# LogicPower.net
KiCad netlist of a schematic drawn in Altium Designer
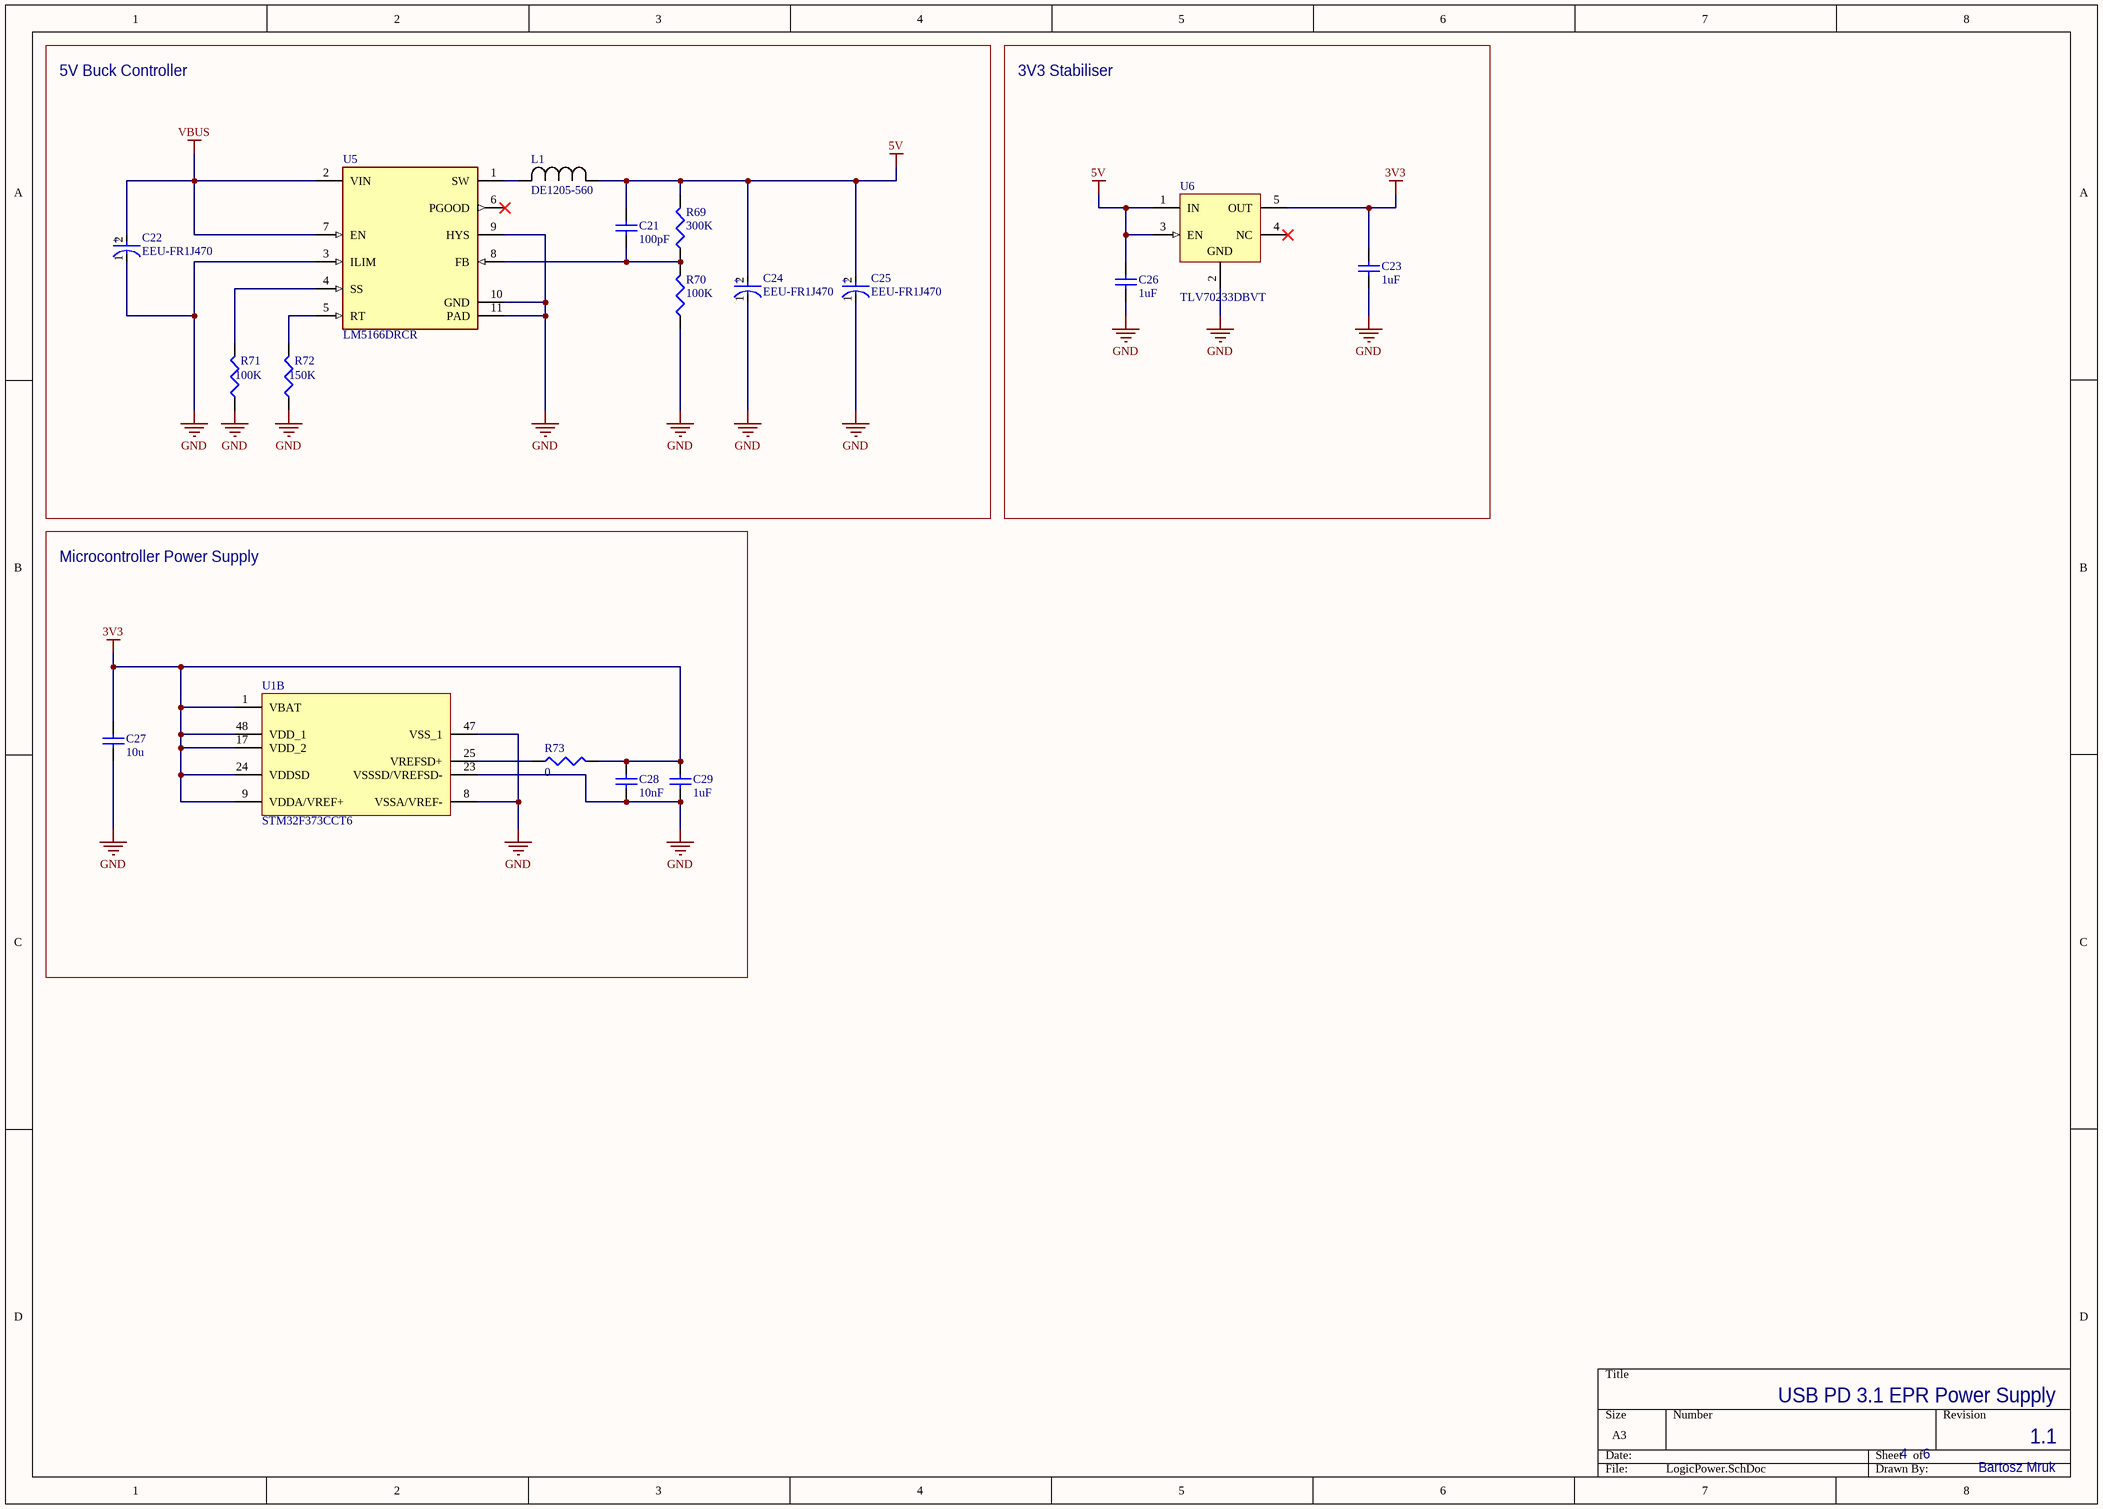
[diagram p0: LogicPower.SchDoc]

(export (version "E")
  (design (tool "Eeschema 10.0.6"))
  (components
    (comp (ref "C21")
      (value "100pF")
      (footprint "C1206")
      (description "Capacitor (Semiconductor SIM Model)")
      (fields (field (name "Comment") "Cap Semi") (field (name "PUBLISHER") "Altium Limited"))
      (libsource (lib "Miscellaneous Devices") (part "Cap Semi"))
    )
    (comp (ref "C22")
      (value "EEU-FR1J470")
      (footprint "FP-EEU-FR1J470-MFG")
      (description "CAP ALUM 47UF 20% 63V RADIAL")
      (fields (field (name "TOLERANCE") "20%") (field (name "VOLTAGE") "63V"))
      (libsource (lib "Altium Content Vault") (part "203bc49f2ac43e59fd269a8c329ed05"))
    )
    (comp (ref "C23")
      (value "1uF")
      (footprint "C1206")
      (description "Capacitor (Semiconductor SIM Model)")
      (fields (field (name "Comment") "Cap Semi") (field (name "PUBLISHER") "Altium Limited"))
      (libsource (lib "Miscellaneous Devices") (part "Cap Semi"))
    )
    (comp (ref "C24")
      (value "EEU-FR1J470")
      (footprint "FP-EEU-FR1J470-MFG")
      (description "CAP ALUM 47UF 20% 63V RADIAL")
      (fields (field (name "TOLERANCE") "20%") (field (name "VOLTAGE") "63V"))
      (libsource (lib "Altium Content Vault") (part "203bc49f2ac43e59fd269a8c329ed05"))
    )
    (comp (ref "C25")
      (value "EEU-FR1J470")
      (footprint "FP-EEU-FR1J470-MFG")
      (description "CAP ALUM 47UF 20% 63V RADIAL")
      (fields (field (name "TOLERANCE") "20%") (field (name "VOLTAGE") "63V"))
      (libsource (lib "Altium Content Vault") (part "203bc49f2ac43e59fd269a8c329ed05"))
    )
    (comp (ref "C26")
      (value "1uF")
      (footprint "C1206")
      (description "Capacitor (Semiconductor SIM Model)")
      (fields (field (name "Comment") "Cap Semi") (field (name "PUBLISHER") "Altium Limited"))
      (libsource (lib "Miscellaneous Devices") (part "Cap Semi"))
    )
    (comp (ref "C27")
      (value "10u")
      (footprint "C1206")
      (description "Capacitor (Semiconductor SIM Model)")
      (fields (field (name "Comment") "Cap Semi") (field (name "PUBLISHER") "Altium Limited"))
      (libsource (lib "Miscellaneous Devices") (part "Cap Semi"))
    )
    (comp (ref "C28")
      (value "10nF")
      (footprint "C1206")
      (description "Capacitor (Semiconductor SIM Model)")
      (fields (field (name "Comment") "Cap Semi") (field (name "PUBLISHER") "Altium Limited"))
      (libsource (lib "Miscellaneous Devices") (part "Cap Semi"))
    )
    (comp (ref "C29")
      (value "1uF")
      (footprint "C1206")
      (description "Capacitor (Semiconductor SIM Model)")
      (fields (field (name "Comment") "Cap Semi") (field (name "PUBLISHER") "Altium Limited"))
      (libsource (lib "Miscellaneous Devices") (part "Cap Semi"))
    )
    (comp (ref "L1")
      (value "DE1205-560")
      (footprint "IND_DE1205_FRC")
      (description "Description")
      (fields (field (name "COPYRIGHT") "Copyright (C) 2025 Ultra Librarian. All rights reserved."))
      (libsource (lib "DE1205-560") (part "DE1205-560"))
    )
    (comp (ref "R69")
      (value "300K")
      (footprint "J1-0603")
      (description "Resistor")
      (fields (field (name "Comment") "Res3") (field (name "PUBLISHER") "Altium Limited"))
      (libsource (lib "Miscellaneous Devices") (part "Res3"))
    )
    (comp (ref "R70")
      (value "100K")
      (footprint "J1-0603")
      (description "Resistor")
      (fields (field (name "Comment") "Res3") (field (name "PUBLISHER") "Altium Limited"))
      (libsource (lib "Miscellaneous Devices") (part "Res3"))
    )
    (comp (ref "R71")
      (value "100K")
      (footprint "J1-0603")
      (description "Resistor")
      (fields (field (name "Comment") "Res3") (field (name "PUBLISHER") "Altium Limited"))
      (libsource (lib "Miscellaneous Devices") (part "Res3"))
    )
    (comp (ref "R72")
      (value "150K")
      (footprint "J1-0603")
      (description "Resistor")
      (fields (field (name "Comment") "Res3") (field (name "PUBLISHER") "Altium Limited"))
      (libsource (lib "Miscellaneous Devices") (part "Res3"))
    )
    (comp (ref "R73")
      (value "0")
      (footprint "J1-0603")
      (description "Resistor")
      (fields (field (name "Comment") "Res3") (field (name "PUBLISHER") "Altium Limited"))
      (libsource (lib "Miscellaneous Devices") (part "Res3"))
    )
    (comp (ref "U1")
      (value "STM32F373CCT6")
      (footprint "STM-LQFP48_M")
      (libsource (lib "Altium Content Vault") (part "MC-ARM-STM32F373-SQ48"))
    )
    (comp (ref "U5")
      (value "LM5166DRCR")
      (footprint "FP-DRC0010J-MFG")
      (description "IC REG BUCK ADJ 500MA 10VSON")
      (fields
        (field (name "OCTOPART") "https://octopart.com/lm5166drcr-texas+instruments-77040222")
        (field (name "MANUFACTURER") "Texas Instruments")
      )
      (libsource (lib "Altium Content Vault") (part "54f7a5ab2ddfda0310545cf18dfc889"))
    )
    (comp (ref "U6")
      (value "TLV70233DBVT")
      (footprint "DBV0005A_M")
      (description "None")
      (libsource (lib "Altium Content Vault") (part "TI-TXX7XXXX-5"))
    )
  )
  (nets
    (net (code "1") (name "3V3") (class "Default")
      (node (ref "C23") (pin "2") (pinfunction "2_2") (pintype "passive"))
      (node (ref "C27") (pin "2") (pinfunction "2_2") (pintype "passive"))
      (node (ref "C28") (pin "2") (pinfunction "2_2") (pintype "passive"))
      (node (ref "C29") (pin "2") (pinfunction "2_2") (pintype "passive"))
      (node (ref "R73") (pin "2") (pinfunction "2_2") (pintype "passive"))
      (node (ref "U1") (pin "1") (pinfunction "VBAT_1") (pintype "power_in"))
      (node (ref "U1") (pin "17") (pinfunction "VDD_2_17") (pintype "power_in"))
      (node (ref "U1") (pin "24") (pinfunction "VDDSD_24") (pintype "power_in"))
      (node (ref "U1") (pin "48") (pinfunction "VDD_1_48") (pintype "power_in"))
      (node (ref "U1") (pin "9") (pinfunction "VDDA/VREF+_9") (pintype "power_in"))
      (node (ref "U6") (pin "5") (pinfunction "OUT_5") (pintype "power_in"))
    )
    (net (code "2") (name "5V") (class "Default")
      (node (ref "C21") (pin "2") (pinfunction "2_2") (pintype "passive"))
      (node (ref "C24") (pin "2") (pinfunction "A_2") (pintype "passive"))
      (node (ref "C25") (pin "2") (pinfunction "A_2") (pintype "passive"))
      (node (ref "C26") (pin "2") (pinfunction "2_2") (pintype "passive"))
      (node (ref "L1") (pin "1") (pinfunction "1_1") (pintype "passive"))
      (node (ref "R69") (pin "2") (pinfunction "2_2") (pintype "passive"))
      (node (ref "U6") (pin "1") (pinfunction "IN_1") (pintype "power_in"))
      (node (ref "U6") (pin "3") (pinfunction "EN_3") (pintype "input"))
    )
    (net (code "3") (name "GND") (class "Default")
      (node (ref "C22") (pin "1") (pinfunction "C_1") (pintype "passive"))
      (node (ref "C23") (pin "1") (pinfunction "1_1") (pintype "passive"))
      (node (ref "C24") (pin "1") (pinfunction "C_1") (pintype "passive"))
      (node (ref "C25") (pin "1") (pinfunction "C_1") (pintype "passive"))
      (node (ref "C26") (pin "1") (pinfunction "1_1") (pintype "passive"))
      (node (ref "C27") (pin "1") (pinfunction "1_1") (pintype "passive"))
      (node (ref "C28") (pin "1") (pinfunction "1_1") (pintype "passive"))
      (node (ref "C29") (pin "1") (pinfunction "1_1") (pintype "passive"))
      (node (ref "R70") (pin "1") (pinfunction "1_1") (pintype "passive"))
      (node (ref "R71") (pin "1") (pinfunction "1_1") (pintype "passive"))
      (node (ref "R72") (pin "1") (pinfunction "1_1") (pintype "passive"))
      (node (ref "U1") (pin "23") (pinfunction "VSSSD/VREFSD-_23") (pintype "power_in"))
      (node (ref "U1") (pin "47") (pinfunction "VSS_1_47") (pintype "power_in"))
      (node (ref "U1") (pin "8") (pinfunction "VSSA/VREF-_8") (pintype "power_in"))
      (node (ref "U5") (pin "10") (pinfunction "GND_10") (pintype "power_in"))
      (node (ref "U5") (pin "11") (pinfunction "PAD_11") (pintype "power_in"))
      (node (ref "U5") (pin "3") (pinfunction "ILIM_3") (pintype "input"))
      (node (ref "U5") (pin "9") (pinfunction "HYS_9") (pintype "passive"))
      (node (ref "U6") (pin "2") (pinfunction "GND_2") (pintype "power_in"))
    )
    (net (code "4") (name "Net-(U1B-VREFSD+)") (class "Default")
      (node (ref "R73") (pin "1") (pinfunction "1_1") (pintype "passive"))
      (node (ref "U1") (pin "25") (pinfunction "VREFSD+_25") (pintype "power_in"))
    )
    (net (code "5") (name "Net-(U5-FB)") (class "Default")
      (node (ref "C21") (pin "1") (pinfunction "1_1") (pintype "passive"))
      (node (ref "R69") (pin "1") (pinfunction "1_1") (pintype "passive"))
      (node (ref "R70") (pin "2") (pinfunction "2_2") (pintype "passive"))
      (node (ref "U5") (pin "8") (pinfunction "FB_8") (pintype "input"))
    )
    (net (code "6") (name "Net-(U5-RT)") (class "Default")
      (node (ref "R72") (pin "2") (pinfunction "2_2") (pintype "passive"))
      (node (ref "U5") (pin "5") (pinfunction "RT_5") (pintype "input"))
    )
    (net (code "7") (name "Net-(U5-SS)") (class "Default")
      (node (ref "R71") (pin "2") (pinfunction "2_2") (pintype "passive"))
      (node (ref "U5") (pin "4") (pinfunction "SS_4") (pintype "input"))
    )
    (net (code "8") (name "Net-(U5-SW)") (class "Default")
      (node (ref "L1") (pin "2") (pinfunction "2_2") (pintype "passive"))
      (node (ref "U5") (pin "1") (pinfunction "SW_1") (pintype "power_in"))
    )
    (net (code "9") (name "VBUS") (class "Default")
      (node (ref "C22") (pin "2") (pinfunction "A_2") (pintype "passive"))
      (node (ref "U5") (pin "2") (pinfunction "VIN_2") (pintype "power_in"))
      (node (ref "U5") (pin "7") (pinfunction "EN_7") (pintype "input"))
    )
    (net (code "10") (name "unconnected-(U5-PGOOD-Pad6)") (class "Default")
      (node (ref "U5") (pin "6") (pinfunction "PGOOD_6") (pintype "output+no_connect"))
    )
    (net (code "11") (name "unconnected-(U6-NC-Pad4)") (class "Default")
      (node (ref "U6") (pin "4") (pinfunction "NC_4") (pintype "passive+no_connect"))
    )
  )
)
